# LNA-SMA.net
KiCad netlist of a schematic drawn in EAGLE
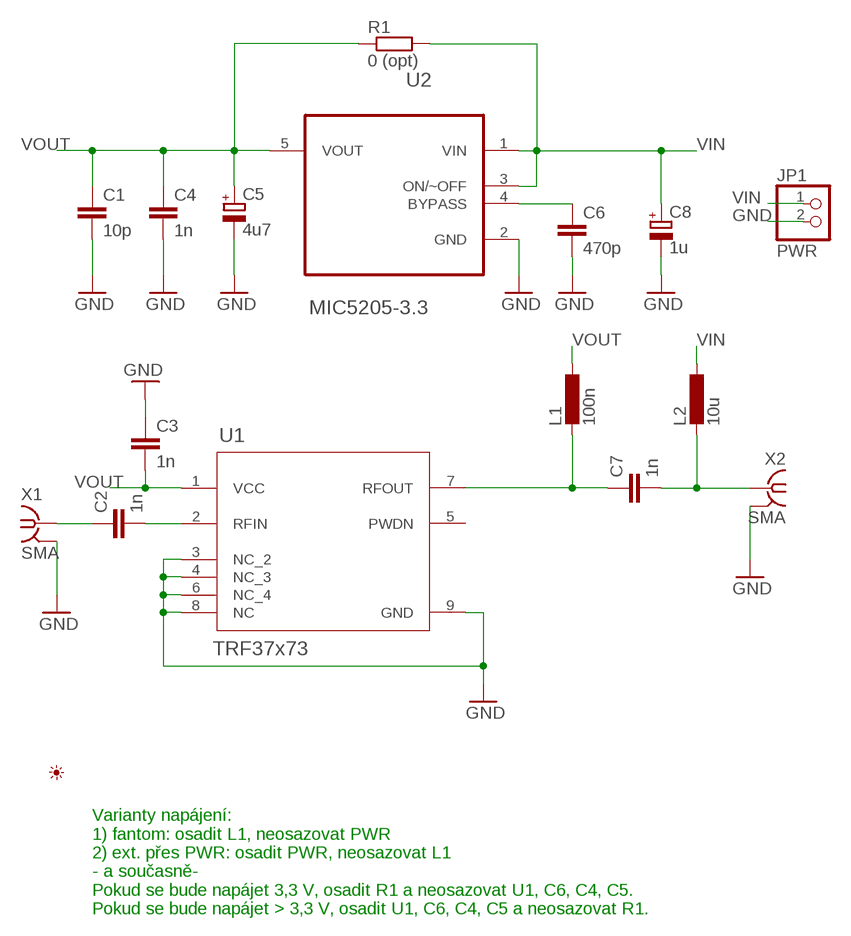
[diagram p0: schematic, sheet 1]

(export (version "E")
  (design (tool "Eeschema 10.0.6"))
  (components
    (comp (ref "C1")
      (value "10p")
      (footprint "eagle-import:C0603")
      (libsource (lib "eagle-import") (part "C-EUC0603"))
    )
    (comp (ref "C2")
      (value "1n")
      (footprint "eagle-import:C0603")
      (libsource (lib "eagle-import") (part "C-EUC0603"))
    )
    (comp (ref "C3")
      (value "1n")
      (footprint "eagle-import:C0603")
      (libsource (lib "eagle-import") (part "C-EUC0603"))
    )
    (comp (ref "C4")
      (value "1n")
      (footprint "eagle-import:C0603")
      (libsource (lib "eagle-import") (part "C-EUC0603"))
    )
    (comp (ref "C5")
      (value "4u7")
      (footprint "eagle-import:SMC_A")
      (libsource (lib "eagle-import") (part "CPOL-EUSMCA"))
    )
    (comp (ref "C6")
      (value "470p")
      (footprint "eagle-import:C0603")
      (libsource (lib "eagle-import") (part "C-EUC0603"))
    )
    (comp (ref "C7")
      (value "1n")
      (footprint "eagle-import:C0603")
      (libsource (lib "eagle-import") (part "C-EUC0603"))
    )
    (comp (ref "C8")
      (value "1u")
      (footprint "eagle-import:SMC_A")
      (libsource (lib "eagle-import") (part "CPOL-EUSMCA"))
    )
    (comp (ref "JP1")
      (value "PWR")
      (footprint "eagle-import:1X02")
      (libsource (lib "eagle-import") (part "PINHD-1X2"))
    )
    (comp (ref "L1")
      (value "100n")
      (footprint "eagle-import:L2012C")
      (libsource (lib "eagle-import") (part "L-EUL2012C"))
    )
    (comp (ref "L2")
      (value "10u")
      (footprint "eagle-import:L2012C")
      (libsource (lib "eagle-import") (part "L-EUL2012C"))
    )
    (comp (ref "R1")
      (value "0 (opt)")
      (footprint "eagle-import:R0603")
      (libsource (lib "eagle-import") (part "R-EU_R0603"))
    )
    (comp (ref "U$1")
      (value "PICTO_1")
      (footprint "eagle-import:PICTO_1")
      (libsource (lib "eagle-import") (part "PICTO_1"))
    )
    (comp (ref "U1")
      (value "TRF37x73")
      (footprint "eagle-import:DSG0008A")
      (fields
        (field (name "ALTERNATEPARTNUMBER") "TRF37D73IDSGT")
        (field (name "MANUFACTURER") "Texas Instruments")
        (field (name "PARTNUMBER") "TRF37D73IDSGR")
      )
      (libsource (lib "eagle-import") (part "TRF37D73IDSGR"))
    )
    (comp (ref "U2")
      (value "MIC5205-3.3")
      (footprint "eagle-import:SOT95P280X145-5N")
      (fields (field (name "MPN") "LP2985A-18DBVJ"))
      (libsource (lib "eagle-import") (part "LP2985A-18DBVJ"))
    )
    (comp (ref "X1")
      (value "SMA")
      (footprint "eagle-import:J502-ND-142-0701-801_806")
      (fields (field (name "MF") "JOHNSON COMPONENTS") (field (name "MPN") "142-0701-801"))
      (libsource (lib "eagle-import") (part "SMA-142-0701-801/806"))
    )
    (comp (ref "X2")
      (value "SMA")
      (footprint "eagle-import:J502-ND-142-0701-801_806")
      (fields (field (name "MF") "JOHNSON COMPONENTS") (field (name "MPN") "142-0701-801"))
      (libsource (lib "eagle-import") (part "SMA-142-0701-801/806"))
    )
  )
  (nets
    (net (code "1") (name "/VIN") (class "Default")
      (node (ref "C8") (pin "+") (pinfunction "+_+") (pintype "passive"))
      (node (ref "JP1") (pin "1") (pinfunction "1_1") (pintype "passive"))
      (node (ref "L2") (pin "1") (pinfunction "1_1") (pintype "passive"))
      (node (ref "R1") (pin "2") (pinfunction "2_2") (pintype "passive"))
      (node (ref "U2") (pin "1") (pinfunction "VIN_1") (pintype "input"))
      (node (ref "U2") (pin "3") (pinfunction "ON/~{OFF}_3") (pintype "input"))
    )
    (net (code "2") (name "/VOUT") (class "Default")
      (node (ref "C1") (pin "1") (pinfunction "1_1") (pintype "passive"))
      (node (ref "C3") (pin "2") (pinfunction "2_2") (pintype "passive"))
      (node (ref "C4") (pin "1") (pinfunction "1_1") (pintype "passive"))
      (node (ref "C5") (pin "+") (pinfunction "+_+") (pintype "passive"))
      (node (ref "L1") (pin "1") (pinfunction "1_1") (pintype "passive"))
      (node (ref "R1") (pin "1") (pinfunction "1_1") (pintype "passive"))
      (node (ref "U1") (pin "1") (pinfunction "VCC_1") (pintype "power_in"))
      (node (ref "U2") (pin "5") (pinfunction "VOUT_5") (pintype "output"))
    )
    (net (code "3") (name "GND") (class "Default")
      (node (ref "C1") (pin "2") (pinfunction "2_2") (pintype "passive"))
      (node (ref "C3") (pin "1") (pinfunction "1_1") (pintype "passive"))
      (node (ref "C4") (pin "2") (pinfunction "2_2") (pintype "passive"))
      (node (ref "C5") (pin "-") (pinfunction "-_-") (pintype "passive"))
      (node (ref "C6") (pin "2") (pinfunction "2_2") (pintype "passive"))
      (node (ref "C8") (pin "-") (pinfunction "-_-") (pintype "passive"))
      (node (ref "JP1") (pin "2") (pinfunction "2_2") (pintype "passive"))
      (node (ref "U1") (pin "3") (pinfunction "NC_2_3") (pintype "passive"))
      (node (ref "U1") (pin "4") (pinfunction "NC_3_4") (pintype "passive"))
      (node (ref "U1") (pin "6") (pinfunction "NC_4_6") (pintype "passive"))
      (node (ref "U1") (pin "8") (pinfunction "NC_8") (pintype "passive"))
      (node (ref "U1") (pin "9") (pinfunction "GND_9") (pintype "power_in"))
      (node (ref "U2") (pin "2") (pinfunction "GND_2") (pintype "passive"))
      (node (ref "X1") (pin "G@1") (pinfunction "2_G@1") (pintype "passive"))
      (node (ref "X1") (pin "G@2") (pinfunction "2_G@2") (pintype "passive"))
      (node (ref "X1") (pin "G@3") (pinfunction "2_G@3") (pintype "passive"))
      (node (ref "X1") (pin "G@4") (pinfunction "2_G@4") (pintype "passive"))
      (node (ref "X2") (pin "G@1") (pinfunction "2_G@1") (pintype "passive"))
      (node (ref "X2") (pin "G@2") (pinfunction "2_G@2") (pintype "passive"))
      (node (ref "X2") (pin "G@3") (pinfunction "2_G@3") (pintype "passive"))
      (node (ref "X2") (pin "G@4") (pinfunction "2_G@4") (pintype "passive"))
    )
    (net (code "4") (name "Net-(C2-Pad1)") (class "Default")
      (node (ref "C2") (pin "1") (pinfunction "1_1") (pintype "passive"))
      (node (ref "X1") (pin "1") (pinfunction "1_1") (pintype "passive"))
    )
    (net (code "5") (name "Net-(C7-Pad2)") (class "Default")
      (node (ref "C7") (pin "2") (pinfunction "2_2") (pintype "passive"))
      (node (ref "L2") (pin "2") (pinfunction "2_2") (pintype "passive"))
      (node (ref "X2") (pin "1") (pinfunction "1_1") (pintype "passive"))
    )
    (net (code "6") (name "Net-(U1-RFIN)") (class "Default")
      (node (ref "C2") (pin "2") (pinfunction "2_2") (pintype "passive"))
      (node (ref "U1") (pin "2") (pinfunction "RFIN_2") (pintype "input"))
    )
    (net (code "7") (name "Net-(U1-RFOUT)") (class "Default")
      (node (ref "C7") (pin "1") (pinfunction "1_1") (pintype "passive"))
      (node (ref "L1") (pin "2") (pinfunction "2_2") (pintype "passive"))
      (node (ref "U1") (pin "7") (pinfunction "RFOUT_7") (pintype "output"))
    )
    (net (code "8") (name "Net-(U2-BYPASS)") (class "Default")
      (node (ref "C6") (pin "1") (pinfunction "1_1") (pintype "passive"))
      (node (ref "U2") (pin "4") (pinfunction "BYPASS_4") (pintype "input"))
    )
    (net (code "9") (name "unconnected-(U1-PWDN-Pad5)") (class "Default")
      (node (ref "U1") (pin "5") (pinfunction "PWDN_5") (pintype "input"))
    )
  )
)
